# FINAL_RNS.net
KiCad netlist of a schematic drawn in EAGLE
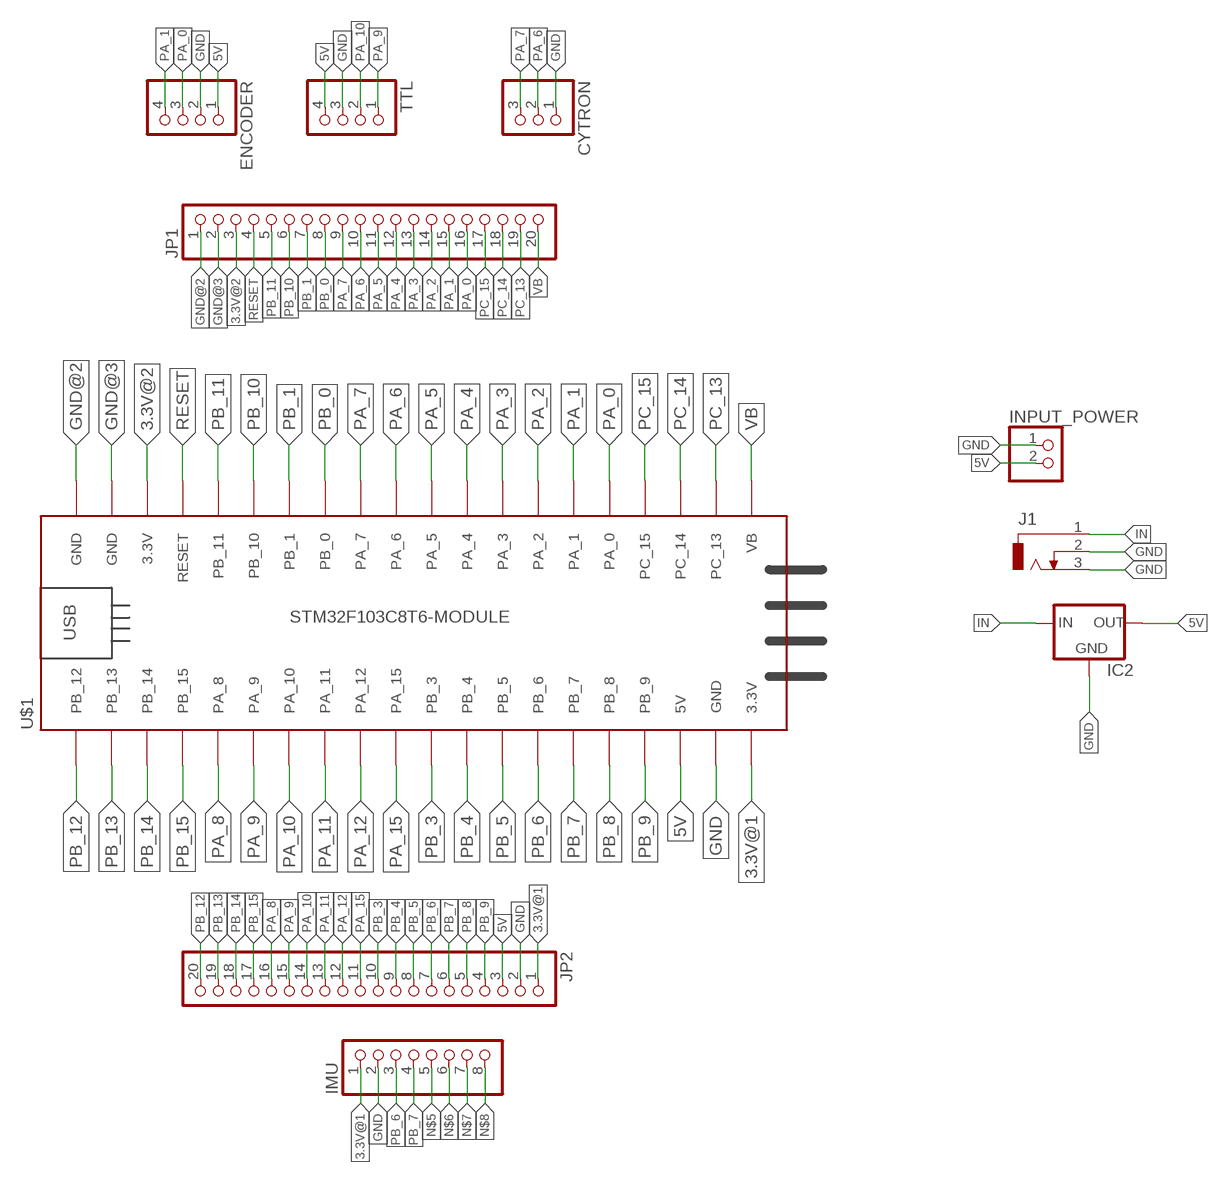
[diagram p0: schematic, sheet 1]

(export (version "E")
  (design (tool "Eeschema 10.0.6"))
  (components
    (comp (ref "CYTRON")
      (value "PINHD-3_DATA")
      (footprint "eagle-import:1X03_DATA")
      (libsource (lib "eagle-import") (part "PINHD-3_DATA"))
    )
    (comp (ref "ENCODER")
      (value "PINHD-4_DATA")
      (footprint "eagle-import:1X04_DATA")
      (libsource (lib "eagle-import") (part "PINHD-4_DATA"))
    )
    (comp (ref "IC2")
      (value "78XXS")
      (footprint "eagle-import:78XXS")
      (libsource (lib "eagle-import") (part "78XXS"))
    )
    (comp (ref "IMU")
      (value "PINHD-1X8")
      (footprint "eagle-import:1X08")
      (libsource (lib "eagle-import") (part "PINHD-1X8"))
    )
    (comp (ref "INPUT_POWER")
      (value "PINHD-2_DATA")
      (footprint "eagle-import:1X02_DATA")
      (libsource (lib "eagle-import") (part "PINHD-2_DATA"))
    )
    (comp (ref "J1")
      (value "CON_JACK")
      (footprint "eagle-import:DCJ0303")
      (libsource (lib "eagle-import") (part "CON_JACK"))
    )
    (comp (ref "JP1")
      (value "PINHD-1X20")
      (footprint "eagle-import:1X20")
      (libsource (lib "eagle-import") (part "PINHD-1X20"))
    )
    (comp (ref "JP2")
      (value "PINHD-1X20")
      (footprint "eagle-import:1X20")
      (libsource (lib "eagle-import") (part "PINHD-1X20"))
    )
    (comp (ref "TTL")
      (value "PINHD-4_DATA")
      (footprint "eagle-import:1X04_DATA")
      (libsource (lib "eagle-import") (part "PINHD-4_DATA"))
    )
    (comp (ref "U$1")
      (value "STM32F103C8T6-MODULE")
      (footprint "eagle-import:STM32F103C8T6-MODULE")
      (libsource (lib "eagle-import") (part "STM32F103C8T6-MODULE"))
    )
  )
  (nets
    (net (code "1") (name "3.3V@1") (class "Default")
      (node (ref "IMU") (pin "1") (pinfunction "1_1") (pintype "passive"))
      (node (ref "JP2") (pin "1") (pinfunction "1_1") (pintype "passive"))
      (node (ref "U$1") (pin "3.3V_1") (pinfunction "3.3V_3.3V_1") (pintype "bidirectional"))
    )
    (net (code "2") (name "3.3V@2") (class "Default")
      (node (ref "JP1") (pin "3") (pinfunction "3_3") (pintype "passive"))
      (node (ref "U$1") (pin "3.3V_2") (pinfunction "3.3V_3.3V_2") (pintype "bidirectional"))
    )
    (net (code "3") (name "5V") (class "Default")
      (node (ref "ENCODER") (pin "1") (pinfunction "1_1") (pintype "passive"))
      (node (ref "IC2") (pin "OUT") (pinfunction "OUT_OUT") (pintype "passive"))
      (node (ref "INPUT_POWER") (pin "2") (pinfunction "2_2") (pintype "passive"))
      (node (ref "JP2") (pin "3") (pinfunction "3_3") (pintype "passive"))
      (node (ref "TTL") (pin "4") (pinfunction "4_4") (pintype "passive"))
      (node (ref "U$1") (pin "5V") (pinfunction "5V_5V") (pintype "bidirectional"))
    )
    (net (code "4") (name "GND") (class "Default")
      (node (ref "CYTRON") (pin "1") (pinfunction "1_1") (pintype "passive"))
      (node (ref "ENCODER") (pin "2") (pinfunction "2_2") (pintype "passive"))
      (node (ref "IC2") (pin "GND") (pinfunction "GND_GND") (pintype "input"))
      (node (ref "IMU") (pin "2") (pinfunction "2_2") (pintype "passive"))
      (node (ref "INPUT_POWER") (pin "1") (pinfunction "1_1") (pintype "passive"))
      (node (ref "J1") (pin "2") (pinfunction "2_2") (pintype "passive"))
      (node (ref "J1") (pin "3") (pinfunction "3_3") (pintype "passive"))
      (node (ref "JP2") (pin "2") (pinfunction "2_2") (pintype "passive"))
      (node (ref "TTL") (pin "3") (pinfunction "3_3") (pintype "passive"))
      (node (ref "U$1") (pin "GND_1") (pinfunction "GND_GND_1") (pintype "bidirectional"))
    )
    (net (code "5") (name "GND@2") (class "Default")
      (node (ref "JP1") (pin "1") (pinfunction "1_1") (pintype "passive"))
      (node (ref "U$1") (pin "GND_3") (pinfunction "GND_GND_3") (pintype "power_in"))
    )
    (net (code "6") (name "GND@3") (class "Default")
      (node (ref "JP1") (pin "2") (pinfunction "2_2") (pintype "passive"))
      (node (ref "U$1") (pin "GND_2") (pinfunction "GND_GND_2") (pintype "bidirectional"))
    )
    (net (code "7") (name "IN") (class "Default")
      (node (ref "IC2") (pin "IN") (pinfunction "IN_IN") (pintype "input"))
      (node (ref "J1") (pin "1") (pinfunction "1_1") (pintype "passive"))
    )
    (net (code "8") (name "N$5") (class "Default")
      (node (ref "IMU") (pin "5") (pinfunction "5_5") (pintype "passive"))
    )
    (net (code "9") (name "N$6") (class "Default")
      (node (ref "IMU") (pin "6") (pinfunction "6_6") (pintype "passive"))
    )
    (net (code "10") (name "N$7") (class "Default")
      (node (ref "IMU") (pin "7") (pinfunction "7_7") (pintype "passive"))
    )
    (net (code "11") (name "N$8") (class "Default")
      (node (ref "IMU") (pin "8") (pinfunction "8_8") (pintype "passive"))
    )
    (net (code "12") (name "PA_0") (class "Default")
      (node (ref "ENCODER") (pin "3") (pinfunction "3_3") (pintype "passive"))
      (node (ref "JP1") (pin "16") (pinfunction "16_16") (pintype "passive"))
      (node (ref "U$1") (pin "PA_0") (pinfunction "PA_0_PA_0") (pintype "bidirectional"))
    )
    (net (code "13") (name "PA_1") (class "Default")
      (node (ref "ENCODER") (pin "4") (pinfunction "4_4") (pintype "passive"))
      (node (ref "JP1") (pin "15") (pinfunction "15_15") (pintype "passive"))
      (node (ref "U$1") (pin "PA_1") (pinfunction "PA_1_PA_1") (pintype "bidirectional"))
    )
    (net (code "14") (name "PA_2") (class "Default")
      (node (ref "JP1") (pin "14") (pinfunction "14_14") (pintype "passive"))
      (node (ref "U$1") (pin "PA_2") (pinfunction "PA_2_PA_2") (pintype "bidirectional"))
    )
    (net (code "15") (name "PA_3") (class "Default")
      (node (ref "JP1") (pin "13") (pinfunction "13_13") (pintype "passive"))
      (node (ref "U$1") (pin "PA_3") (pinfunction "PA_3_PA_3") (pintype "bidirectional"))
    )
    (net (code "16") (name "PA_4") (class "Default")
      (node (ref "JP1") (pin "12") (pinfunction "12_12") (pintype "passive"))
      (node (ref "U$1") (pin "PA_4") (pinfunction "PA_4_PA_4") (pintype "bidirectional"))
    )
    (net (code "17") (name "PA_5") (class "Default")
      (node (ref "JP1") (pin "11") (pinfunction "11_11") (pintype "passive"))
      (node (ref "U$1") (pin "PA_5") (pinfunction "PA_5_PA_5") (pintype "bidirectional"))
    )
    (net (code "18") (name "PA_6") (class "Default")
      (node (ref "CYTRON") (pin "2") (pinfunction "2_2") (pintype "passive"))
      (node (ref "JP1") (pin "10") (pinfunction "10_10") (pintype "passive"))
      (node (ref "U$1") (pin "PA_6") (pinfunction "PA_6_PA_6") (pintype "bidirectional"))
    )
    (net (code "19") (name "PA_7") (class "Default")
      (node (ref "CYTRON") (pin "3") (pinfunction "3_3") (pintype "passive"))
      (node (ref "JP1") (pin "9") (pinfunction "9_9") (pintype "passive"))
      (node (ref "U$1") (pin "PA_7") (pinfunction "PA_7_PA_7") (pintype "bidirectional"))
    )
    (net (code "20") (name "PA_8") (class "Default")
      (node (ref "JP2") (pin "16") (pinfunction "16_16") (pintype "passive"))
      (node (ref "U$1") (pin "PA_8") (pinfunction "PA_8_PA_8") (pintype "bidirectional"))
    )
    (net (code "21") (name "PA_9") (class "Default")
      (node (ref "JP2") (pin "15") (pinfunction "15_15") (pintype "passive"))
      (node (ref "TTL") (pin "1") (pinfunction "1_1") (pintype "passive"))
      (node (ref "U$1") (pin "PA_9") (pinfunction "PA_9_PA_9") (pintype "bidirectional"))
    )
    (net (code "22") (name "PA_10") (class "Default")
      (node (ref "JP2") (pin "14") (pinfunction "14_14") (pintype "passive"))
      (node (ref "TTL") (pin "2") (pinfunction "2_2") (pintype "passive"))
      (node (ref "U$1") (pin "PA_10") (pinfunction "PA_10_PA_10") (pintype "bidirectional"))
    )
    (net (code "23") (name "PA_11") (class "Default")
      (node (ref "JP2") (pin "13") (pinfunction "13_13") (pintype "passive"))
      (node (ref "U$1") (pin "PA_11") (pinfunction "PA_11_PA_11") (pintype "bidirectional"))
    )
    (net (code "24") (name "PA_12") (class "Default")
      (node (ref "JP2") (pin "12") (pinfunction "12_12") (pintype "passive"))
      (node (ref "U$1") (pin "PA_12") (pinfunction "PA_12_PA_12") (pintype "bidirectional"))
    )
    (net (code "25") (name "PA_15") (class "Default")
      (node (ref "JP2") (pin "11") (pinfunction "11_11") (pintype "passive"))
      (node (ref "U$1") (pin "PA_15") (pinfunction "PA_15_PA_15") (pintype "bidirectional"))
    )
    (net (code "26") (name "PB_0") (class "Default")
      (node (ref "JP1") (pin "8") (pinfunction "8_8") (pintype "passive"))
      (node (ref "U$1") (pin "PB_0") (pinfunction "PB_0_PB_0") (pintype "bidirectional"))
    )
    (net (code "27") (name "PB_1") (class "Default")
      (node (ref "JP1") (pin "7") (pinfunction "7_7") (pintype "passive"))
      (node (ref "U$1") (pin "PB_1") (pinfunction "PB_1_PB_1") (pintype "bidirectional"))
    )
    (net (code "28") (name "PB_3") (class "Default")
      (node (ref "JP2") (pin "10") (pinfunction "10_10") (pintype "passive"))
      (node (ref "U$1") (pin "PB_3") (pinfunction "PB_3_PB_3") (pintype "bidirectional"))
    )
    (net (code "29") (name "PB_4") (class "Default")
      (node (ref "JP2") (pin "9") (pinfunction "9_9") (pintype "passive"))
      (node (ref "U$1") (pin "PB_4") (pinfunction "PB_4_PB_4") (pintype "bidirectional"))
    )
    (net (code "30") (name "PB_5") (class "Default")
      (node (ref "JP2") (pin "8") (pinfunction "8_8") (pintype "passive"))
      (node (ref "U$1") (pin "PB_5") (pinfunction "PB_5_PB_5") (pintype "bidirectional"))
    )
    (net (code "31") (name "PB_6") (class "Default")
      (node (ref "IMU") (pin "3") (pinfunction "3_3") (pintype "passive"))
      (node (ref "JP2") (pin "7") (pinfunction "7_7") (pintype "passive"))
      (node (ref "U$1") (pin "PB_6") (pinfunction "PB_6_PB_6") (pintype "bidirectional"))
    )
    (net (code "32") (name "PB_7") (class "Default")
      (node (ref "IMU") (pin "4") (pinfunction "4_4") (pintype "passive"))
      (node (ref "JP2") (pin "6") (pinfunction "6_6") (pintype "passive"))
      (node (ref "U$1") (pin "PB_7") (pinfunction "PB_7_PB_7") (pintype "bidirectional"))
    )
    (net (code "33") (name "PB_8") (class "Default")
      (node (ref "JP2") (pin "5") (pinfunction "5_5") (pintype "passive"))
      (node (ref "U$1") (pin "PB_8") (pinfunction "PB_8_PB_8") (pintype "bidirectional"))
    )
    (net (code "34") (name "PB_9") (class "Default")
      (node (ref "JP2") (pin "4") (pinfunction "4_4") (pintype "passive"))
      (node (ref "U$1") (pin "PB_9") (pinfunction "PB_9_PB_9") (pintype "bidirectional"))
    )
    (net (code "35") (name "PB_10") (class "Default")
      (node (ref "JP1") (pin "6") (pinfunction "6_6") (pintype "passive"))
      (node (ref "U$1") (pin "PB_10") (pinfunction "PB_10_PB_10") (pintype "bidirectional"))
    )
    (net (code "36") (name "PB_11") (class "Default")
      (node (ref "JP1") (pin "5") (pinfunction "5_5") (pintype "passive"))
      (node (ref "U$1") (pin "PB_11") (pinfunction "PB_11_PB_11") (pintype "bidirectional"))
    )
    (net (code "37") (name "PB_12") (class "Default")
      (node (ref "JP2") (pin "20") (pinfunction "20_20") (pintype "passive"))
      (node (ref "U$1") (pin "PB_12") (pinfunction "PB_12_PB_12") (pintype "bidirectional"))
    )
    (net (code "38") (name "PB_13") (class "Default")
      (node (ref "JP2") (pin "19") (pinfunction "19_19") (pintype "passive"))
      (node (ref "U$1") (pin "PB_13") (pinfunction "PB_13_PB_13") (pintype "bidirectional"))
    )
    (net (code "39") (name "PB_14") (class "Default")
      (node (ref "JP2") (pin "18") (pinfunction "18_18") (pintype "passive"))
      (node (ref "U$1") (pin "PB_14") (pinfunction "PB_14_PB_14") (pintype "bidirectional"))
    )
    (net (code "40") (name "PB_15") (class "Default")
      (node (ref "JP2") (pin "17") (pinfunction "17_17") (pintype "passive"))
      (node (ref "U$1") (pin "PB_15") (pinfunction "PB_15_PB_15") (pintype "bidirectional"))
    )
    (net (code "41") (name "PC_13") (class "Default")
      (node (ref "JP1") (pin "19") (pinfunction "19_19") (pintype "passive"))
      (node (ref "U$1") (pin "PC_13") (pinfunction "PC_13_PC_13") (pintype "bidirectional"))
    )
    (net (code "42") (name "PC_14") (class "Default")
      (node (ref "JP1") (pin "18") (pinfunction "18_18") (pintype "passive"))
      (node (ref "U$1") (pin "PC_14") (pinfunction "PC_14_PC_14") (pintype "bidirectional"))
    )
    (net (code "43") (name "PC_15") (class "Default")
      (node (ref "JP1") (pin "17") (pinfunction "17_17") (pintype "passive"))
      (node (ref "U$1") (pin "PC_15") (pinfunction "PC_15_PC_15") (pintype "bidirectional"))
    )
    (net (code "44") (name "RESET") (class "Default")
      (node (ref "JP1") (pin "4") (pinfunction "4_4") (pintype "passive"))
      (node (ref "U$1") (pin "RESET") (pinfunction "RESET_RESET") (pintype "bidirectional"))
    )
    (net (code "45") (name "VB") (class "Default")
      (node (ref "JP1") (pin "20") (pinfunction "20_20") (pintype "passive"))
      (node (ref "U$1") (pin "VB") (pinfunction "VB_VB") (pintype "bidirectional"))
    )
  )
)
